# pmod-cape.net
KiCad netlist of a schematic drawn in EAGLE
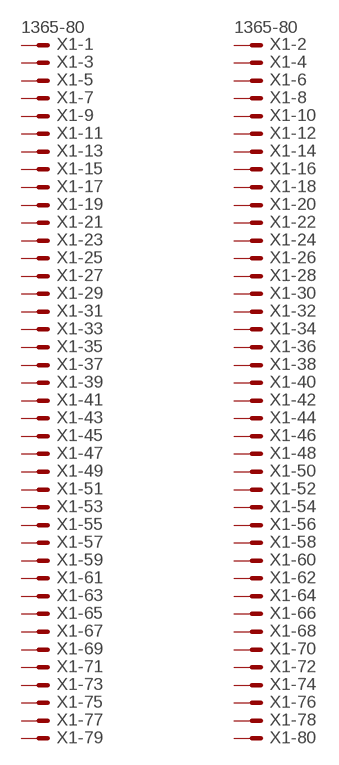
[diagram p0: schematic, sheet 1]
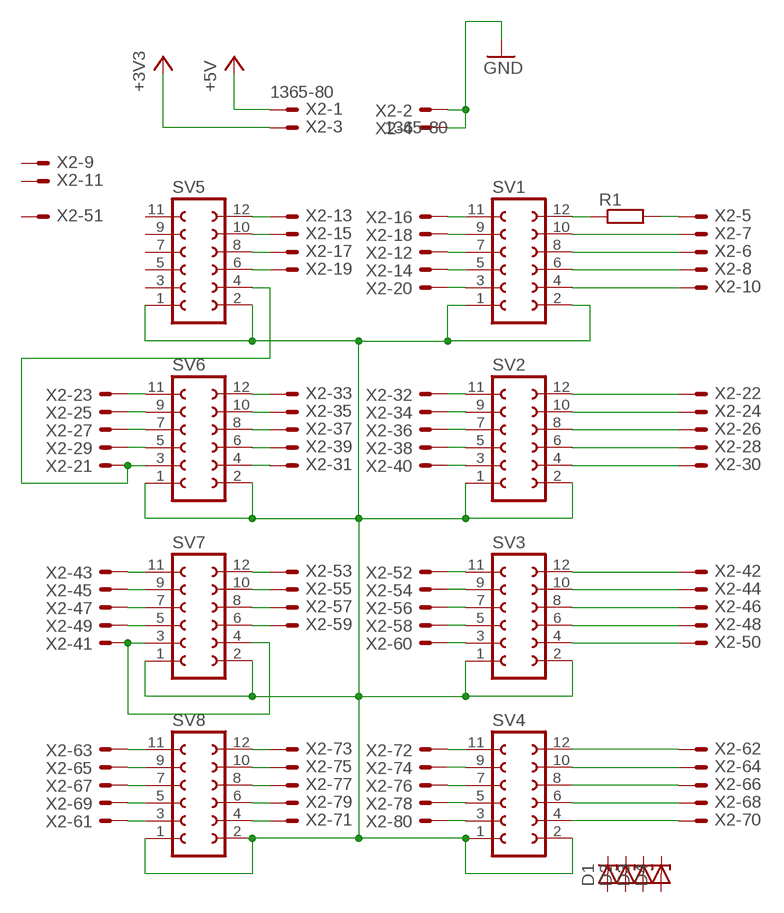
[diagram p1: schematic, sheet 2]

(export (version "E")
  (design (tool "Eeschema 10.0.6"))
  (components
    (comp (ref "D1")
      (value "ZENER-DIODESOD80C")
      (footprint "eagle-import:SOD80C")
      (libsource (lib "eagle-import") (part "ZENER-DIODESOD80C"))
    )
    (comp (ref "D2")
      (value "ZENER-DIODESOD80C")
      (footprint "eagle-import:SOD80C")
      (libsource (lib "eagle-import") (part "ZENER-DIODESOD80C"))
    )
    (comp (ref "D3")
      (value "ZENER-DIODESOD80C")
      (footprint "eagle-import:SOD80C")
      (libsource (lib "eagle-import") (part "ZENER-DIODESOD80C"))
    )
    (comp (ref "D4")
      (value "ZENER-DIODESOD80C")
      (footprint "eagle-import:SOD80C")
      (libsource (lib "eagle-import") (part "ZENER-DIODESOD80C"))
    )
    (comp (ref "R1")
      (value "R-EU_R0805")
      (footprint "eagle-import:R0805")
      (libsource (lib "eagle-import") (part "R-EU_R0805"))
    )
    (comp (ref "SV1")
      (value "FE06-2W")
      (footprint "eagle-import:FE06-2W")
      (libsource (lib "eagle-import") (part "FE06-2W"))
    )
    (comp (ref "SV2")
      (value "FE06-2W")
      (footprint "eagle-import:FE06-2W")
      (libsource (lib "eagle-import") (part "FE06-2W"))
    )
    (comp (ref "SV3")
      (value "FE06-2W")
      (footprint "eagle-import:FE06-2W")
      (libsource (lib "eagle-import") (part "FE06-2W"))
    )
    (comp (ref "SV4")
      (value "FE06-2W")
      (footprint "eagle-import:FE06-2W")
      (libsource (lib "eagle-import") (part "FE06-2W"))
    )
    (comp (ref "SV5")
      (value "FE06-2W")
      (footprint "eagle-import:FE06-2W")
      (libsource (lib "eagle-import") (part "FE06-2W"))
    )
    (comp (ref "SV6")
      (value "FE06-2W")
      (footprint "eagle-import:FE06-2W")
      (libsource (lib "eagle-import") (part "FE06-2W"))
    )
    (comp (ref "SV7")
      (value "FE06-2W")
      (footprint "eagle-import:FE06-2W")
      (libsource (lib "eagle-import") (part "FE06-2W"))
    )
    (comp (ref "SV8")
      (value "FE06-2W")
      (footprint "eagle-import:FE06-2W")
      (libsource (lib "eagle-import") (part "FE06-2W"))
    )
    (comp (ref "X2")
      (value "1365-80")
      (footprint "eagle-import:1365-80")
      (libsource (lib "eagle-import") (part "1365-80"))
    )
    (comp (ref "X1")
      (value "1365-80")
      (footprint "eagle-import:1365-80")
      (libsource (lib "eagle-import") (part "1365-80"))
    )
  )
  (nets
    (net (code "1") (name "+3V3") (class "Default")
      (node (ref "X2") (pin "3") (pinfunction "S_3") (pintype "passive"))
    )
    (net (code "2") (name "+5V") (class "Default")
      (node (ref "X2") (pin "1") (pinfunction "S_1") (pintype "passive"))
    )
    (net (code "3") (name "GND") (class "Default")
      (node (ref "X2") (pin "2") (pinfunction "S_2") (pintype "passive"))
      (node (ref "X2") (pin "4") (pinfunction "S_4") (pintype "passive"))
    )
    (net (code "4") (name "Net-(R1-Pad1)") (class "Default")
      (node (ref "R1") (pin "1") (pinfunction "1_1") (pintype "passive"))
      (node (ref "SV1") (pin "12") (pinfunction "12_12") (pintype "passive"))
    )
    (net (code "5") (name "Net-(SV1-Pad1)") (class "Default")
      (node (ref "SV1") (pin "1") (pinfunction "1_1") (pintype "passive"))
      (node (ref "SV1") (pin "2") (pinfunction "2_2") (pintype "passive"))
      (node (ref "SV2") (pin "1") (pinfunction "1_1") (pintype "passive"))
      (node (ref "SV2") (pin "2") (pinfunction "2_2") (pintype "passive"))
      (node (ref "SV3") (pin "1") (pinfunction "1_1") (pintype "passive"))
      (node (ref "SV3") (pin "2") (pinfunction "2_2") (pintype "passive"))
      (node (ref "SV4") (pin "1") (pinfunction "1_1") (pintype "passive"))
      (node (ref "SV4") (pin "2") (pinfunction "2_2") (pintype "passive"))
      (node (ref "SV5") (pin "1") (pinfunction "1_1") (pintype "passive"))
      (node (ref "SV5") (pin "2") (pinfunction "2_2") (pintype "passive"))
      (node (ref "SV6") (pin "1") (pinfunction "1_1") (pintype "passive"))
      (node (ref "SV6") (pin "2") (pinfunction "2_2") (pintype "passive"))
      (node (ref "SV7") (pin "1") (pinfunction "1_1") (pintype "passive"))
      (node (ref "SV7") (pin "2") (pinfunction "2_2") (pintype "passive"))
      (node (ref "SV8") (pin "1") (pinfunction "1_1") (pintype "passive"))
      (node (ref "SV8") (pin "2") (pinfunction "2_2") (pintype "passive"))
    )
    (net (code "6") (name "Net-(X2AA-S)") (class "Default")
      (node (ref "SV6") (pin "12") (pinfunction "12_12") (pintype "passive"))
      (node (ref "X2") (pin "33") (pinfunction "S_33") (pintype "passive"))
    )
    (net (code "7") (name "Net-(X2AB-S)") (class "Default")
      (node (ref "SV2") (pin "9") (pinfunction "9_9") (pintype "passive"))
      (node (ref "X2") (pin "34") (pinfunction "S_34") (pintype "passive"))
    )
    (net (code "8") (name "Net-(X2AC-S)") (class "Default")
      (node (ref "SV6") (pin "10") (pinfunction "10_10") (pintype "passive"))
      (node (ref "X2") (pin "35") (pinfunction "S_35") (pintype "passive"))
    )
    (net (code "9") (name "Net-(X2AD-S)") (class "Default")
      (node (ref "SV2") (pin "7") (pinfunction "7_7") (pintype "passive"))
      (node (ref "X2") (pin "36") (pinfunction "S_36") (pintype "passive"))
    )
    (net (code "10") (name "Net-(X2AE-S)") (class "Default")
      (node (ref "SV6") (pin "8") (pinfunction "8_8") (pintype "passive"))
      (node (ref "X2") (pin "37") (pinfunction "S_37") (pintype "passive"))
    )
    (net (code "11") (name "Net-(X2AF-S)") (class "Default")
      (node (ref "SV2") (pin "5") (pinfunction "5_5") (pintype "passive"))
      (node (ref "X2") (pin "38") (pinfunction "S_38") (pintype "passive"))
    )
    (net (code "12") (name "Net-(X2AG-S)") (class "Default")
      (node (ref "SV6") (pin "6") (pinfunction "6_6") (pintype "passive"))
      (node (ref "X2") (pin "39") (pinfunction "S_39") (pintype "passive"))
    )
    (net (code "13") (name "Net-(X2AI-S)") (class "Default")
      (node (ref "SV2") (pin "3") (pinfunction "3_3") (pintype "passive"))
      (node (ref "X2") (pin "40") (pinfunction "S_40") (pintype "passive"))
    )
    (net (code "14") (name "Net-(X2AJ-S)") (class "Default")
      (node (ref "SV7") (pin "3") (pinfunction "3_3") (pintype "passive"))
      (node (ref "SV7") (pin "4") (pinfunction "4_4") (pintype "passive"))
      (node (ref "X2") (pin "41") (pinfunction "S_41") (pintype "passive"))
    )
    (net (code "15") (name "Net-(X2AK-S)") (class "Default")
      (node (ref "SV3") (pin "12") (pinfunction "12_12") (pintype "passive"))
      (node (ref "X2") (pin "42") (pinfunction "S_42") (pintype "passive"))
    )
    (net (code "16") (name "Net-(X2AL-S)") (class "Default")
      (node (ref "SV7") (pin "11") (pinfunction "11_11") (pintype "passive"))
      (node (ref "X2") (pin "43") (pinfunction "S_43") (pintype "passive"))
    )
    (net (code "17") (name "Net-(X2AM-S)") (class "Default")
      (node (ref "SV3") (pin "10") (pinfunction "10_10") (pintype "passive"))
      (node (ref "X2") (pin "44") (pinfunction "S_44") (pintype "passive"))
    )
    (net (code "18") (name "Net-(X2AN-S)") (class "Default")
      (node (ref "SV7") (pin "9") (pinfunction "9_9") (pintype "passive"))
      (node (ref "X2") (pin "45") (pinfunction "S_45") (pintype "passive"))
    )
    (net (code "19") (name "Net-(X2AO-S)") (class "Default")
      (node (ref "SV3") (pin "8") (pinfunction "8_8") (pintype "passive"))
      (node (ref "X2") (pin "46") (pinfunction "S_46") (pintype "passive"))
    )
    (net (code "20") (name "Net-(X2AP-S)") (class "Default")
      (node (ref "SV7") (pin "7") (pinfunction "7_7") (pintype "passive"))
      (node (ref "X2") (pin "47") (pinfunction "S_47") (pintype "passive"))
    )
    (net (code "21") (name "Net-(X2AQ-S)") (class "Default")
      (node (ref "SV3") (pin "6") (pinfunction "6_6") (pintype "passive"))
      (node (ref "X2") (pin "48") (pinfunction "S_48") (pintype "passive"))
    )
    (net (code "22") (name "Net-(X2AR-S)") (class "Default")
      (node (ref "SV7") (pin "5") (pinfunction "5_5") (pintype "passive"))
      (node (ref "X2") (pin "49") (pinfunction "S_49") (pintype "passive"))
    )
    (net (code "23") (name "Net-(X2AS-S)") (class "Default")
      (node (ref "R1") (pin "2") (pinfunction "2_2") (pintype "passive"))
      (node (ref "X2") (pin "5") (pinfunction "S_5") (pintype "passive"))
    )
    (net (code "24") (name "Net-(X2AT-S)") (class "Default")
      (node (ref "SV3") (pin "4") (pinfunction "4_4") (pintype "passive"))
      (node (ref "X2") (pin "50") (pinfunction "S_50") (pintype "passive"))
    )
    (net (code "25") (name "Net-(X2AV-S)") (class "Default")
      (node (ref "SV3") (pin "11") (pinfunction "11_11") (pintype "passive"))
      (node (ref "X2") (pin "52") (pinfunction "S_52") (pintype "passive"))
    )
    (net (code "26") (name "Net-(X2AW-S)") (class "Default")
      (node (ref "SV7") (pin "12") (pinfunction "12_12") (pintype "passive"))
      (node (ref "X2") (pin "53") (pinfunction "S_53") (pintype "passive"))
    )
    (net (code "27") (name "Net-(X2AX-S)") (class "Default")
      (node (ref "SV3") (pin "9") (pinfunction "9_9") (pintype "passive"))
      (node (ref "X2") (pin "54") (pinfunction "S_54") (pintype "passive"))
    )
    (net (code "28") (name "Net-(X2AY-S)") (class "Default")
      (node (ref "SV7") (pin "10") (pinfunction "10_10") (pintype "passive"))
      (node (ref "X2") (pin "55") (pinfunction "S_55") (pintype "passive"))
    )
    (net (code "29") (name "Net-(X2AZ-S)") (class "Default")
      (node (ref "SV3") (pin "7") (pinfunction "7_7") (pintype "passive"))
      (node (ref "X2") (pin "56") (pinfunction "S_56") (pintype "passive"))
    )
    (net (code "30") (name "Net-(X2B-S)") (class "Default")
      (node (ref "SV1") (pin "4") (pinfunction "4_4") (pintype "passive"))
      (node (ref "X2") (pin "10") (pinfunction "S_10") (pintype "passive"))
    )
    (net (code "31") (name "Net-(X2BA-S)") (class "Default")
      (node (ref "SV7") (pin "8") (pinfunction "8_8") (pintype "passive"))
      (node (ref "X2") (pin "57") (pinfunction "S_57") (pintype "passive"))
    )
    (net (code "32") (name "Net-(X2BB-S)") (class "Default")
      (node (ref "SV3") (pin "5") (pinfunction "5_5") (pintype "passive"))
      (node (ref "X2") (pin "58") (pinfunction "S_58") (pintype "passive"))
    )
    (net (code "33") (name "Net-(X2BC-S)") (class "Default")
      (node (ref "SV7") (pin "6") (pinfunction "6_6") (pintype "passive"))
      (node (ref "X2") (pin "59") (pinfunction "S_59") (pintype "passive"))
    )
    (net (code "34") (name "Net-(X2BD-S)") (class "Default")
      (node (ref "SV1") (pin "8") (pinfunction "8_8") (pintype "passive"))
      (node (ref "X2") (pin "6") (pinfunction "S_6") (pintype "passive"))
    )
    (net (code "35") (name "Net-(X2BE-S)") (class "Default")
      (node (ref "SV3") (pin "3") (pinfunction "3_3") (pintype "passive"))
      (node (ref "X2") (pin "60") (pinfunction "S_60") (pintype "passive"))
    )
    (net (code "36") (name "Net-(X2BF-S)") (class "Default")
      (node (ref "SV8") (pin "3") (pinfunction "3_3") (pintype "passive"))
      (node (ref "X2") (pin "61") (pinfunction "S_61") (pintype "passive"))
    )
    (net (code "37") (name "Net-(X2BG-S)") (class "Default")
      (node (ref "SV4") (pin "12") (pinfunction "12_12") (pintype "passive"))
      (node (ref "X2") (pin "62") (pinfunction "S_62") (pintype "passive"))
    )
    (net (code "38") (name "Net-(X2BH-S)") (class "Default")
      (node (ref "SV8") (pin "11") (pinfunction "11_11") (pintype "passive"))
      (node (ref "X2") (pin "63") (pinfunction "S_63") (pintype "passive"))
    )
    (net (code "39") (name "Net-(X2BI-S)") (class "Default")
      (node (ref "SV4") (pin "10") (pinfunction "10_10") (pintype "passive"))
      (node (ref "X2") (pin "64") (pinfunction "S_64") (pintype "passive"))
    )
    (net (code "40") (name "Net-(X2BJ-S)") (class "Default")
      (node (ref "SV8") (pin "9") (pinfunction "9_9") (pintype "passive"))
      (node (ref "X2") (pin "65") (pinfunction "S_65") (pintype "passive"))
    )
    (net (code "41") (name "Net-(X2BK-S)") (class "Default")
      (node (ref "SV4") (pin "8") (pinfunction "8_8") (pintype "passive"))
      (node (ref "X2") (pin "66") (pinfunction "S_66") (pintype "passive"))
    )
    (net (code "42") (name "Net-(X2BL-S)") (class "Default")
      (node (ref "SV8") (pin "7") (pinfunction "7_7") (pintype "passive"))
      (node (ref "X2") (pin "67") (pinfunction "S_67") (pintype "passive"))
    )
    (net (code "43") (name "Net-(X2BM-S)") (class "Default")
      (node (ref "SV4") (pin "6") (pinfunction "6_6") (pintype "passive"))
      (node (ref "X2") (pin "68") (pinfunction "S_68") (pintype "passive"))
    )
    (net (code "44") (name "Net-(X2BN-S)") (class "Default")
      (node (ref "SV8") (pin "5") (pinfunction "5_5") (pintype "passive"))
      (node (ref "X2") (pin "69") (pinfunction "S_69") (pintype "passive"))
    )
    (net (code "45") (name "Net-(X2BO-S)") (class "Default")
      (node (ref "SV1") (pin "10") (pinfunction "10_10") (pintype "passive"))
      (node (ref "X2") (pin "7") (pinfunction "S_7") (pintype "passive"))
    )
    (net (code "46") (name "Net-(X2BP-S)") (class "Default")
      (node (ref "SV4") (pin "4") (pinfunction "4_4") (pintype "passive"))
      (node (ref "X2") (pin "70") (pinfunction "S_70") (pintype "passive"))
    )
    (net (code "47") (name "Net-(X2BQ-S)") (class "Default")
      (node (ref "SV8") (pin "4") (pinfunction "4_4") (pintype "passive"))
      (node (ref "X2") (pin "71") (pinfunction "S_71") (pintype "passive"))
    )
    (net (code "48") (name "Net-(X2BR-S)") (class "Default")
      (node (ref "SV4") (pin "11") (pinfunction "11_11") (pintype "passive"))
      (node (ref "X2") (pin "72") (pinfunction "S_72") (pintype "passive"))
    )
    (net (code "49") (name "Net-(X2BS-S)") (class "Default")
      (node (ref "SV8") (pin "12") (pinfunction "12_12") (pintype "passive"))
      (node (ref "X2") (pin "73") (pinfunction "S_73") (pintype "passive"))
    )
    (net (code "50") (name "Net-(X2BT-S)") (class "Default")
      (node (ref "SV4") (pin "9") (pinfunction "9_9") (pintype "passive"))
      (node (ref "X2") (pin "74") (pinfunction "S_74") (pintype "passive"))
    )
    (net (code "51") (name "Net-(X2BU-S)") (class "Default")
      (node (ref "SV8") (pin "10") (pinfunction "10_10") (pintype "passive"))
      (node (ref "X2") (pin "75") (pinfunction "S_75") (pintype "passive"))
    )
    (net (code "52") (name "Net-(X2BV-S)") (class "Default")
      (node (ref "SV4") (pin "7") (pinfunction "7_7") (pintype "passive"))
      (node (ref "X2") (pin "76") (pinfunction "S_76") (pintype "passive"))
    )
    (net (code "53") (name "Net-(X2BW-S)") (class "Default")
      (node (ref "SV8") (pin "8") (pinfunction "8_8") (pintype "passive"))
      (node (ref "X2") (pin "77") (pinfunction "S_77") (pintype "passive"))
    )
    (net (code "54") (name "Net-(X2BX-S)") (class "Default")
      (node (ref "SV4") (pin "5") (pinfunction "5_5") (pintype "passive"))
      (node (ref "X2") (pin "78") (pinfunction "S_78") (pintype "passive"))
    )
    (net (code "55") (name "Net-(X2BY-S)") (class "Default")
      (node (ref "SV8") (pin "6") (pinfunction "6_6") (pintype "passive"))
      (node (ref "X2") (pin "79") (pinfunction "S_79") (pintype "passive"))
    )
    (net (code "56") (name "Net-(X2BZ-S)") (class "Default")
      (node (ref "SV1") (pin "6") (pinfunction "6_6") (pintype "passive"))
      (node (ref "X2") (pin "8") (pinfunction "S_8") (pintype "passive"))
    )
    (net (code "57") (name "Net-(X2CA-S)") (class "Default")
      (node (ref "SV4") (pin "3") (pinfunction "3_3") (pintype "passive"))
      (node (ref "X2") (pin "80") (pinfunction "S_80") (pintype "passive"))
    )
    (net (code "58") (name "Net-(X2D-S)") (class "Default")
      (node (ref "SV1") (pin "7") (pinfunction "7_7") (pintype "passive"))
      (node (ref "X2") (pin "12") (pinfunction "S_12") (pintype "passive"))
    )
    (net (code "59") (name "Net-(X2E-S)") (class "Default")
      (node (ref "SV5") (pin "12") (pinfunction "12_12") (pintype "passive"))
      (node (ref "X2") (pin "13") (pinfunction "S_13") (pintype "passive"))
    )
    (net (code "60") (name "Net-(X2F-S)") (class "Default")
      (node (ref "SV1") (pin "5") (pinfunction "5_5") (pintype "passive"))
      (node (ref "X2") (pin "14") (pinfunction "S_14") (pintype "passive"))
    )
    (net (code "61") (name "Net-(X2G-S)") (class "Default")
      (node (ref "SV5") (pin "10") (pinfunction "10_10") (pintype "passive"))
      (node (ref "X2") (pin "15") (pinfunction "S_15") (pintype "passive"))
    )
    (net (code "62") (name "Net-(X2H-S)") (class "Default")
      (node (ref "SV1") (pin "11") (pinfunction "11_11") (pintype "passive"))
      (node (ref "X2") (pin "16") (pinfunction "S_16") (pintype "passive"))
    )
    (net (code "63") (name "Net-(X2I-S)") (class "Default")
      (node (ref "SV5") (pin "8") (pinfunction "8_8") (pintype "passive"))
      (node (ref "X2") (pin "17") (pinfunction "S_17") (pintype "passive"))
    )
    (net (code "64") (name "Net-(X2J-S)") (class "Default")
      (node (ref "SV1") (pin "9") (pinfunction "9_9") (pintype "passive"))
      (node (ref "X2") (pin "18") (pinfunction "S_18") (pintype "passive"))
    )
    (net (code "65") (name "Net-(X2K-S)") (class "Default")
      (node (ref "SV5") (pin "6") (pinfunction "6_6") (pintype "passive"))
      (node (ref "X2") (pin "19") (pinfunction "S_19") (pintype "passive"))
    )
    (net (code "66") (name "Net-(X2M-S)") (class "Default")
      (node (ref "SV1") (pin "3") (pinfunction "3_3") (pintype "passive"))
      (node (ref "X2") (pin "20") (pinfunction "S_20") (pintype "passive"))
    )
    (net (code "67") (name "Net-(X2N-S)") (class "Default")
      (node (ref "SV5") (pin "4") (pinfunction "4_4") (pintype "passive"))
      (node (ref "SV6") (pin "3") (pinfunction "3_3") (pintype "passive"))
      (node (ref "X2") (pin "21") (pinfunction "S_21") (pintype "passive"))
    )
    (net (code "68") (name "Net-(X2O-S)") (class "Default")
      (node (ref "SV2") (pin "12") (pinfunction "12_12") (pintype "passive"))
      (node (ref "X2") (pin "22") (pinfunction "S_22") (pintype "passive"))
    )
    (net (code "69") (name "Net-(X2P-S)") (class "Default")
      (node (ref "SV6") (pin "11") (pinfunction "11_11") (pintype "passive"))
      (node (ref "X2") (pin "23") (pinfunction "S_23") (pintype "passive"))
    )
    (net (code "70") (name "Net-(X2Q-S)") (class "Default")
      (node (ref "SV2") (pin "10") (pinfunction "10_10") (pintype "passive"))
      (node (ref "X2") (pin "24") (pinfunction "S_24") (pintype "passive"))
    )
    (net (code "71") (name "Net-(X2R-S)") (class "Default")
      (node (ref "SV6") (pin "9") (pinfunction "9_9") (pintype "passive"))
      (node (ref "X2") (pin "25") (pinfunction "S_25") (pintype "passive"))
    )
    (net (code "72") (name "Net-(X2S-S)") (class "Default")
      (node (ref "SV2") (pin "8") (pinfunction "8_8") (pintype "passive"))
      (node (ref "X2") (pin "26") (pinfunction "S_26") (pintype "passive"))
    )
    (net (code "73") (name "Net-(X2T-S)") (class "Default")
      (node (ref "SV6") (pin "7") (pinfunction "7_7") (pintype "passive"))
      (node (ref "X2") (pin "27") (pinfunction "S_27") (pintype "passive"))
    )
    (net (code "74") (name "Net-(X2U-S)") (class "Default")
      (node (ref "SV2") (pin "6") (pinfunction "6_6") (pintype "passive"))
      (node (ref "X2") (pin "28") (pinfunction "S_28") (pintype "passive"))
    )
    (net (code "75") (name "Net-(X2V-S)") (class "Default")
      (node (ref "SV6") (pin "5") (pinfunction "5_5") (pintype "passive"))
      (node (ref "X2") (pin "29") (pinfunction "S_29") (pintype "passive"))
    )
    (net (code "76") (name "Net-(X2X-S)") (class "Default")
      (node (ref "SV2") (pin "4") (pinfunction "4_4") (pintype "passive"))
      (node (ref "X2") (pin "30") (pinfunction "S_30") (pintype "passive"))
    )
    (net (code "77") (name "Net-(X2Y-S)") (class "Default")
      (node (ref "SV6") (pin "4") (pinfunction "4_4") (pintype "passive"))
      (node (ref "X2") (pin "31") (pinfunction "S_31") (pintype "passive"))
    )
    (net (code "78") (name "Net-(X2Z-S)") (class "Default")
      (node (ref "SV2") (pin "11") (pinfunction "11_11") (pintype "passive"))
      (node (ref "X2") (pin "32") (pinfunction "S_32") (pintype "passive"))
    )
    (net (code "79") (name "unconnected-(D1-PadA)") (class "Default")
      (node (ref "D1") (pin "A") (pinfunction "A_A") (pintype "passive"))
    )
    (net (code "80") (name "unconnected-(D1-PadC)") (class "Default")
      (node (ref "D1") (pin "C") (pinfunction "C_C") (pintype "passive"))
    )
    (net (code "81") (name "unconnected-(D2-PadA)") (class "Default")
      (node (ref "D2") (pin "A") (pinfunction "A_A") (pintype "passive"))
    )
    (net (code "82") (name "unconnected-(D2-PadC)") (class "Default")
      (node (ref "D2") (pin "C") (pinfunction "C_C") (pintype "passive"))
    )
    (net (code "83") (name "unconnected-(D3-PadA)") (class "Default")
      (node (ref "D3") (pin "A") (pinfunction "A_A") (pintype "passive"))
    )
    (net (code "84") (name "unconnected-(D3-PadC)") (class "Default")
      (node (ref "D3") (pin "C") (pinfunction "C_C") (pintype "passive"))
    )
    (net (code "85") (name "unconnected-(D4-PadA)") (class "Default")
      (node (ref "D4") (pin "A") (pinfunction "A_A") (pintype "passive"))
    )
    (net (code "86") (name "unconnected-(D4-PadC)") (class "Default")
      (node (ref "D4") (pin "C") (pinfunction "C_C") (pintype "passive"))
    )
    (net (code "87") (name "unconnected-(SV5-Pad3)") (class "Default")
      (node (ref "SV5") (pin "3") (pinfunction "3_3") (pintype "passive"))
    )
    (net (code "88") (name "unconnected-(SV5-Pad5)") (class "Default")
      (node (ref "SV5") (pin "5") (pinfunction "5_5") (pintype "passive"))
    )
    (net (code "89") (name "unconnected-(SV5-Pad7)") (class "Default")
      (node (ref "SV5") (pin "7") (pinfunction "7_7") (pintype "passive"))
    )
    (net (code "90") (name "unconnected-(SV5-Pad9)") (class "Default")
      (node (ref "SV5") (pin "9") (pinfunction "9_9") (pintype "passive"))
    )
    (net (code "91") (name "unconnected-(SV5-Pad11)") (class "Default")
      (node (ref "SV5") (pin "11") (pinfunction "11_11") (pintype "passive"))
    )
    (net (code "92") (name "unconnected-(X1A-S-Pad1)") (class "Default")
      (node (ref "X1") (pin "1") (pinfunction "S_1") (pintype "passive"))
    )
    (net (code "93") (name "unconnected-(X1AA-S-Pad33)") (class "Default")
      (node (ref "X1") (pin "33") (pinfunction "S_33") (pintype "passive"))
    )
    (net (code "94") (name "unconnected-(X1AB-S-Pad34)") (class "Default")
      (node (ref "X1") (pin "34") (pinfunction "S_34") (pintype "passive"))
    )
    (net (code "95") (name "unconnected-(X1AC-S-Pad35)") (class "Default")
      (node (ref "X1") (pin "35") (pinfunction "S_35") (pintype "passive"))
    )
    (net (code "96") (name "unconnected-(X1AD-S-Pad36)") (class "Default")
      (node (ref "X1") (pin "36") (pinfunction "S_36") (pintype "passive"))
    )
    (net (code "97") (name "unconnected-(X1AE-S-Pad37)") (class "Default")
      (node (ref "X1") (pin "37") (pinfunction "S_37") (pintype "passive"))
    )
    (net (code "98") (name "unconnected-(X1AF-S-Pad38)") (class "Default")
      (node (ref "X1") (pin "38") (pinfunction "S_38") (pintype "passive"))
    )
    (net (code "99") (name "unconnected-(X1AG-S-Pad39)") (class "Default")
      (node (ref "X1") (pin "39") (pinfunction "S_39") (pintype "passive"))
    )
    (net (code "100") (name "unconnected-(X1AH-S-Pad4)") (class "Default")
      (node (ref "X1") (pin "4") (pinfunction "S_4") (pintype "passive"))
    )
    (net (code "101") (name "unconnected-(X1AI-S-Pad40)") (class "Default")
      (node (ref "X1") (pin "40") (pinfunction "S_40") (pintype "passive"))
    )
    (net (code "102") (name "unconnected-(X1AJ-S-Pad41)") (class "Default")
      (node (ref "X1") (pin "41") (pinfunction "S_41") (pintype "passive"))
    )
    (net (code "103") (name "unconnected-(X1AK-S-Pad42)") (class "Default")
      (node (ref "X1") (pin "42") (pinfunction "S_42") (pintype "passive"))
    )
    (net (code "104") (name "unconnected-(X1AL-S-Pad43)") (class "Default")
      (node (ref "X1") (pin "43") (pinfunction "S_43") (pintype "passive"))
    )
    (net (code "105") (name "unconnected-(X1AM-S-Pad44)") (class "Default")
      (node (ref "X1") (pin "44") (pinfunction "S_44") (pintype "passive"))
    )
    (net (code "106") (name "unconnected-(X1AN-S-Pad45)") (class "Default")
      (node (ref "X1") (pin "45") (pinfunction "S_45") (pintype "passive"))
    )
    (net (code "107") (name "unconnected-(X1AO-S-Pad46)") (class "Default")
      (node (ref "X1") (pin "46") (pinfunction "S_46") (pintype "passive"))
    )
    (net (code "108") (name "unconnected-(X1AP-S-Pad47)") (class "Default")
      (node (ref "X1") (pin "47") (pinfunction "S_47") (pintype "passive"))
    )
    (net (code "109") (name "unconnected-(X1AQ-S-Pad48)") (class "Default")
      (node (ref "X1") (pin "48") (pinfunction "S_48") (pintype "passive"))
    )
    (net (code "110") (name "unconnected-(X1AR-S-Pad49)") (class "Default")
      (node (ref "X1") (pin "49") (pinfunction "S_49") (pintype "passive"))
    )
    (net (code "111") (name "unconnected-(X1AS-S-Pad5)") (class "Default")
      (node (ref "X1") (pin "5") (pinfunction "S_5") (pintype "passive"))
    )
    (net (code "112") (name "unconnected-(X1AT-S-Pad50)") (class "Default")
      (node (ref "X1") (pin "50") (pinfunction "S_50") (pintype "passive"))
    )
    (net (code "113") (name "unconnected-(X1AU-S-Pad51)") (class "Default")
      (node (ref "X1") (pin "51") (pinfunction "S_51") (pintype "passive"))
    )
    (net (code "114") (name "unconnected-(X1AV-S-Pad52)") (class "Default")
      (node (ref "X1") (pin "52") (pinfunction "S_52") (pintype "passive"))
    )
    (net (code "115") (name "unconnected-(X1AW-S-Pad53)") (class "Default")
      (node (ref "X1") (pin "53") (pinfunction "S_53") (pintype "passive"))
    )
    (net (code "116") (name "unconnected-(X1AX-S-Pad54)") (class "Default")
      (node (ref "X1") (pin "54") (pinfunction "S_54") (pintype "passive"))
    )
    (net (code "117") (name "unconnected-(X1AY-S-Pad55)") (class "Default")
      (node (ref "X1") (pin "55") (pinfunction "S_55") (pintype "passive"))
    )
    (net (code "118") (name "unconnected-(X1AZ-S-Pad56)") (class "Default")
      (node (ref "X1") (pin "56") (pinfunction "S_56") (pintype "passive"))
    )
    (net (code "119") (name "unconnected-(X1B-S-Pad10)") (class "Default")
      (node (ref "X1") (pin "10") (pinfunction "S_10") (pintype "passive"))
    )
    (net (code "120") (name "unconnected-(X1BA-S-Pad57)") (class "Default")
      (node (ref "X1") (pin "57") (pinfunction "S_57") (pintype "passive"))
    )
    (net (code "121") (name "unconnected-(X1BB-S-Pad58)") (class "Default")
      (node (ref "X1") (pin "58") (pinfunction "S_58") (pintype "passive"))
    )
    (net (code "122") (name "unconnected-(X1BC-S-Pad59)") (class "Default")
      (node (ref "X1") (pin "59") (pinfunction "S_59") (pintype "passive"))
    )
    (net (code "123") (name "unconnected-(X1BD-S-Pad6)") (class "Default")
      (node (ref "X1") (pin "6") (pinfunction "S_6") (pintype "passive"))
    )
    (net (code "124") (name "unconnected-(X1BE-S-Pad60)") (class "Default")
      (node (ref "X1") (pin "60") (pinfunction "S_60") (pintype "passive"))
    )
    (net (code "125") (name "unconnected-(X1BF-S-Pad61)") (class "Default")
      (node (ref "X1") (pin "61") (pinfunction "S_61") (pintype "passive"))
    )
    (net (code "126") (name "unconnected-(X1BG-S-Pad62)") (class "Default")
      (node (ref "X1") (pin "62") (pinfunction "S_62") (pintype "passive"))
    )
    (net (code "127") (name "unconnected-(X1BH-S-Pad63)") (class "Default")
      (node (ref "X1") (pin "63") (pinfunction "S_63") (pintype "passive"))
    )
    (net (code "128") (name "unconnected-(X1BI-S-Pad64)") (class "Default")
      (node (ref "X1") (pin "64") (pinfunction "S_64") (pintype "passive"))
    )
    (net (code "129") (name "unconnected-(X1BJ-S-Pad65)") (class "Default")
      (node (ref "X1") (pin "65") (pinfunction "S_65") (pintype "passive"))
    )
    (net (code "130") (name "unconnected-(X1BK-S-Pad66)") (class "Default")
      (node (ref "X1") (pin "66") (pinfunction "S_66") (pintype "passive"))
    )
    (net (code "131") (name "unconnected-(X1BL-S-Pad67)") (class "Default")
      (node (ref "X1") (pin "67") (pinfunction "S_67") (pintype "passive"))
    )
    (net (code "132") (name "unconnected-(X1BM-S-Pad68)") (class "Default")
      (node (ref "X1") (pin "68") (pinfunction "S_68") (pintype "passive"))
    )
    (net (code "133") (name "unconnected-(X1BN-S-Pad69)") (class "Default")
      (node (ref "X1") (pin "69") (pinfunction "S_69") (pintype "passive"))
    )
    (net (code "134") (name "unconnected-(X1BO-S-Pad7)") (class "Default")
      (node (ref "X1") (pin "7") (pinfunction "S_7") (pintype "passive"))
    )
    (net (code "135") (name "unconnected-(X1BP-S-Pad70)") (class "Default")
      (node (ref "X1") (pin "70") (pinfunction "S_70") (pintype "passive"))
    )
    (net (code "136") (name "unconnected-(X1BQ-S-Pad71)") (class "Default")
      (node (ref "X1") (pin "71") (pinfunction "S_71") (pintype "passive"))
    )
    (net (code "137") (name "unconnected-(X1BR-S-Pad72)") (class "Default")
      (node (ref "X1") (pin "72") (pinfunction "S_72") (pintype "passive"))
    )
    (net (code "138") (name "unconnected-(X1BS-S-Pad73)") (class "Default")
      (node (ref "X1") (pin "73") (pinfunction "S_73") (pintype "passive"))
    )
    (net (code "139") (name "unconnected-(X1BT-S-Pad74)") (class "Default")
      (node (ref "X1") (pin "74") (pinfunction "S_74") (pintype "passive"))
    )
    (net (code "140") (name "unconnected-(X1BU-S-Pad75)") (class "Default")
      (node (ref "X1") (pin "75") (pinfunction "S_75") (pintype "passive"))
    )
    (net (code "141") (name "unconnected-(X1BV-S-Pad76)") (class "Default")
      (node (ref "X1") (pin "76") (pinfunction "S_76") (pintype "passive"))
    )
    (net (code "142") (name "unconnected-(X1BW-S-Pad77)") (class "Default")
      (node (ref "X1") (pin "77") (pinfunction "S_77") (pintype "passive"))
    )
    (net (code "143") (name "unconnected-(X1BX-S-Pad78)") (class "Default")
      (node (ref "X1") (pin "78") (pinfunction "S_78") (pintype "passive"))
    )
    (net (code "144") (name "unconnected-(X1BY-S-Pad79)") (class "Default")
      (node (ref "X1") (pin "79") (pinfunction "S_79") (pintype "passive"))
    )
    (net (code "145") (name "unconnected-(X1BZ-S-Pad8)") (class "Default")
      (node (ref "X1") (pin "8") (pinfunction "S_8") (pintype "passive"))
    )
    (net (code "146") (name "unconnected-(X1C-S-Pad11)") (class "Default")
      (node (ref "X1") (pin "11") (pinfunction "S_11") (pintype "passive"))
    )
    (net (code "147") (name "unconnected-(X1CA-S-Pad80)") (class "Default")
      (node (ref "X1") (pin "80") (pinfunction "S_80") (pintype "passive"))
    )
    (net (code "148") (name "unconnected-(X1CB-S-Pad9)") (class "Default")
      (node (ref "X1") (pin "9") (pinfunction "S_9") (pintype "passive"))
    )
    (net (code "149") (name "unconnected-(X1D-S-Pad12)") (class "Default")
      (node (ref "X1") (pin "12") (pinfunction "S_12") (pintype "passive"))
    )
    (net (code "150") (name "unconnected-(X1E-S-Pad13)") (class "Default")
      (node (ref "X1") (pin "13") (pinfunction "S_13") (pintype "passive"))
    )
    (net (code "151") (name "unconnected-(X1F-S-Pad14)") (class "Default")
      (node (ref "X1") (pin "14") (pinfunction "S_14") (pintype "passive"))
    )
    (net (code "152") (name "unconnected-(X1G-S-Pad15)") (class "Default")
      (node (ref "X1") (pin "15") (pinfunction "S_15") (pintype "passive"))
    )
    (net (code "153") (name "unconnected-(X1H-S-Pad16)") (class "Default")
      (node (ref "X1") (pin "16") (pinfunction "S_16") (pintype "passive"))
    )
    (net (code "154") (name "unconnected-(X1I-S-Pad17)") (class "Default")
      (node (ref "X1") (pin "17") (pinfunction "S_17") (pintype "passive"))
    )
    (net (code "155") (name "unconnected-(X1J-S-Pad18)") (class "Default")
      (node (ref "X1") (pin "18") (pinfunction "S_18") (pintype "passive"))
    )
    (net (code "156") (name "unconnected-(X1K-S-Pad19)") (class "Default")
      (node (ref "X1") (pin "19") (pinfunction "S_19") (pintype "passive"))
    )
    (net (code "157") (name "unconnected-(X1L-S-Pad2)") (class "Default")
      (node (ref "X1") (pin "2") (pinfunction "S_2") (pintype "passive"))
    )
    (net (code "158") (name "unconnected-(X1M-S-Pad20)") (class "Default")
      (node (ref "X1") (pin "20") (pinfunction "S_20") (pintype "passive"))
    )
    (net (code "159") (name "unconnected-(X1N-S-Pad21)") (class "Default")
      (node (ref "X1") (pin "21") (pinfunction "S_21") (pintype "passive"))
    )
    (net (code "160") (name "unconnected-(X1O-S-Pad22)") (class "Default")
      (node (ref "X1") (pin "22") (pinfunction "S_22") (pintype "passive"))
    )
    (net (code "161") (name "unconnected-(X1P-S-Pad23)") (class "Default")
      (node (ref "X1") (pin "23") (pinfunction "S_23") (pintype "passive"))
    )
    (net (code "162") (name "unconnected-(X1Q-S-Pad24)") (class "Default")
      (node (ref "X1") (pin "24") (pinfunction "S_24") (pintype "passive"))
    )
    (net (code "163") (name "unconnected-(X1R-S-Pad25)") (class "Default")
      (node (ref "X1") (pin "25") (pinfunction "S_25") (pintype "passive"))
    )
    (net (code "164") (name "unconnected-(X1S-S-Pad26)") (class "Default")
      (node (ref "X1") (pin "26") (pinfunction "S_26") (pintype "passive"))
    )
    (net (code "165") (name "unconnected-(X1T-S-Pad27)") (class "Default")
      (node (ref "X1") (pin "27") (pinfunction "S_27") (pintype "passive"))
    )
    (net (code "166") (name "unconnected-(X1U-S-Pad28)") (class "Default")
      (node (ref "X1") (pin "28") (pinfunction "S_28") (pintype "passive"))
    )
    (net (code "167") (name "unconnected-(X1V-S-Pad29)") (class "Default")
      (node (ref "X1") (pin "29") (pinfunction "S_29") (pintype "passive"))
    )
    (net (code "168") (name "unconnected-(X1W-S-Pad3)") (class "Default")
      (node (ref "X1") (pin "3") (pinfunction "S_3") (pintype "passive"))
    )
    (net (code "169") (name "unconnected-(X1X-S-Pad30)") (class "Default")
      (node (ref "X1") (pin "30") (pinfunction "S_30") (pintype "passive"))
    )
    (net (code "170") (name "unconnected-(X1Y-S-Pad31)") (class "Default")
      (node (ref "X1") (pin "31") (pinfunction "S_31") (pintype "passive"))
    )
    (net (code "171") (name "unconnected-(X1Z-S-Pad32)") (class "Default")
      (node (ref "X1") (pin "32") (pinfunction "S_32") (pintype "passive"))
    )
    (net (code "172") (name "unconnected-(X2AU-S-Pad51)") (class "Default")
      (node (ref "X2") (pin "51") (pinfunction "S_51") (pintype "passive"))
    )
    (net (code "173") (name "unconnected-(X2C-S-Pad11)") (class "Default")
      (node (ref "X2") (pin "11") (pinfunction "S_11") (pintype "passive"))
    )
    (net (code "174") (name "unconnected-(X2CB-S-Pad9)") (class "Default")
      (node (ref "X2") (pin "9") (pinfunction "S_9") (pintype "passive"))
    )
  )
)
